# Atmega.net
KiCad netlist of a schematic drawn in EAGLE
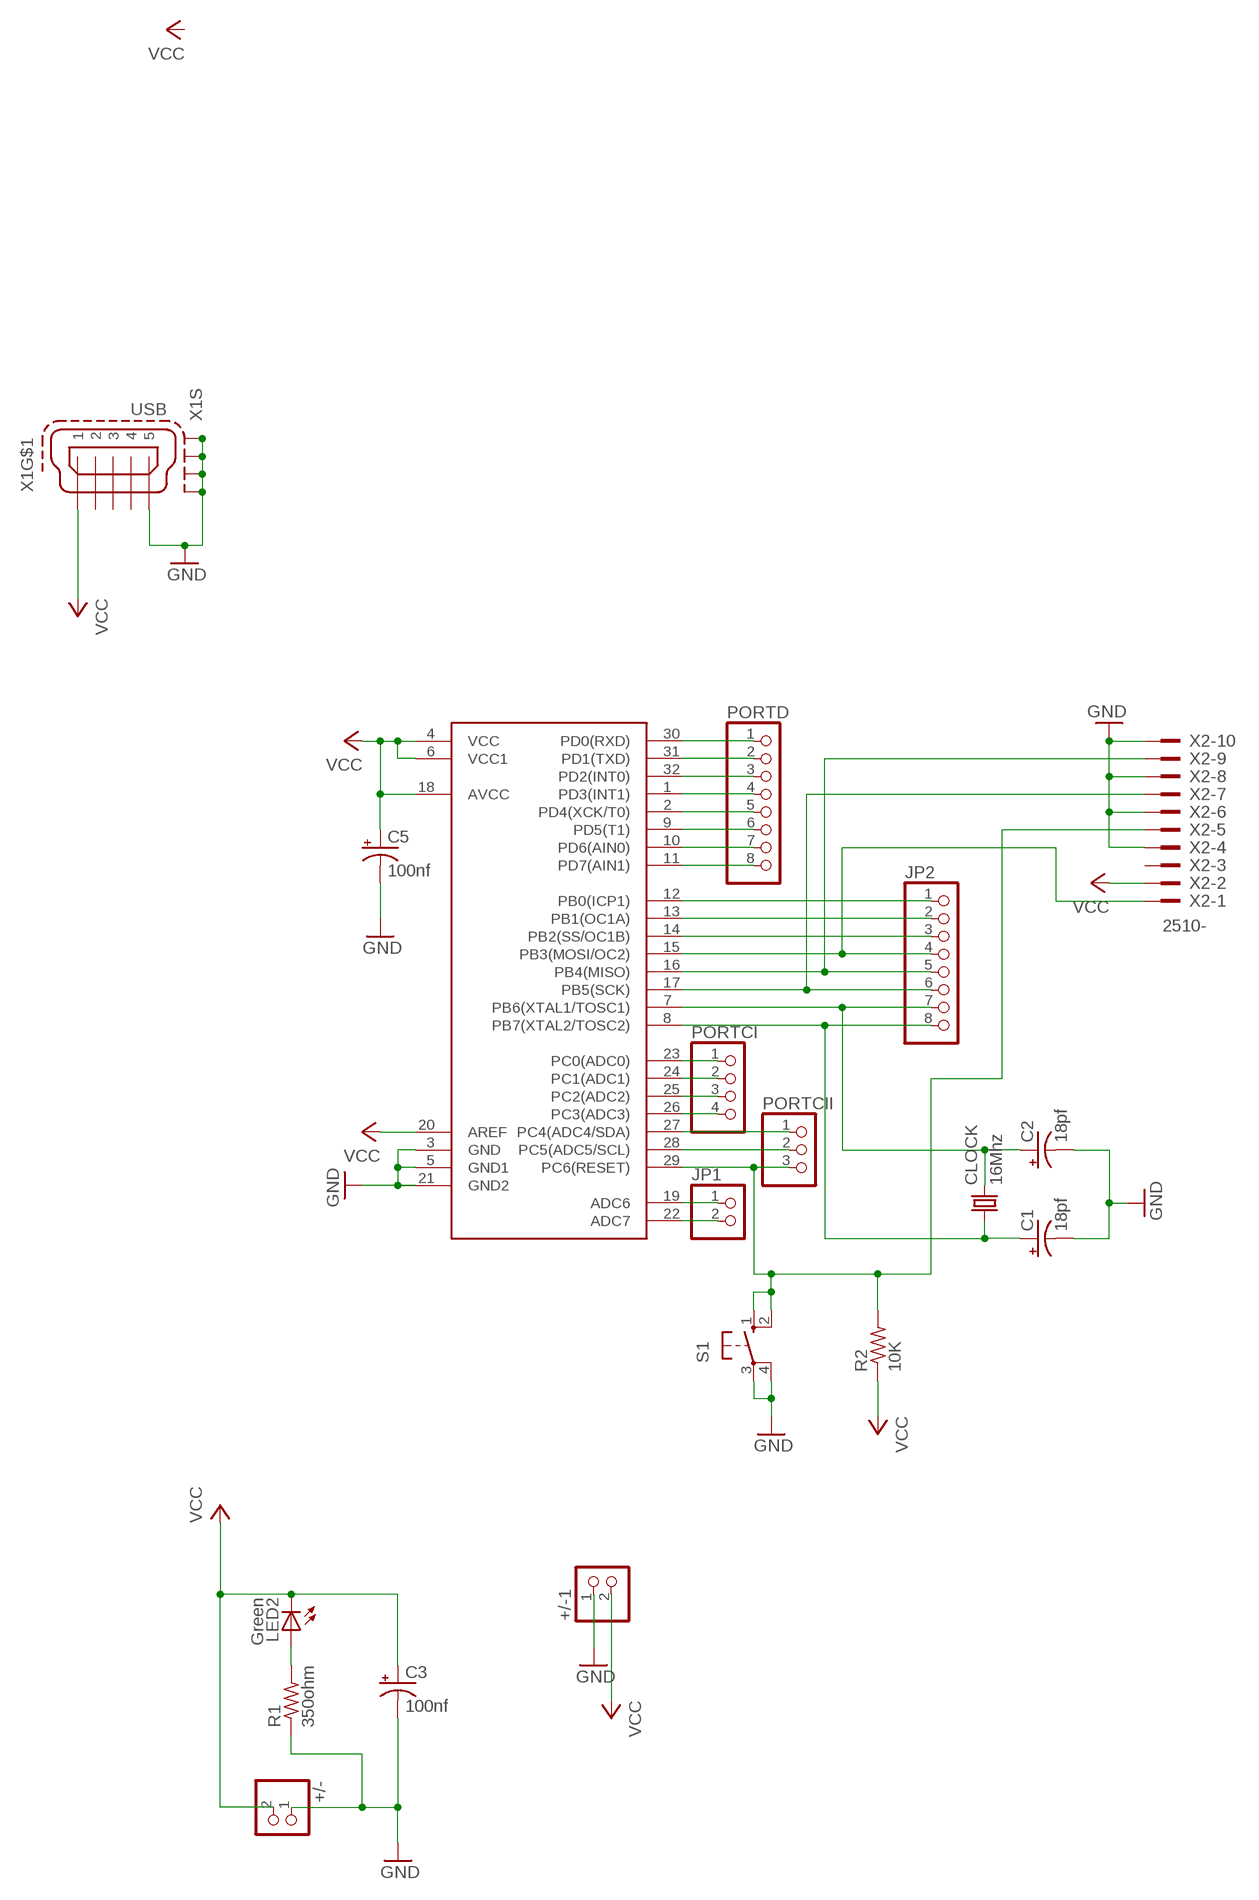
[diagram p0: schematic, sheet 1]

(export (version "E")
  (design (tool "Eeschema 10.0.6"))
  (components
    (comp (ref "+/-")
      (value "PINHD-1X2")
      (footprint "eagle-import:1X02")
      (libsource (lib "eagle-import") (part "PINHD-1X2"))
    )
    (comp (ref "+/-1")
      (value "PINHD-1X2")
      (footprint "eagle-import:1X02")
      (libsource (lib "eagle-import") (part "PINHD-1X2"))
    )
    (comp (ref "C1")
      (value "18pf")
      (footprint "eagle-import:SMC_Z")
      (libsource (lib "eagle-import") (part "CPOL-USSMCZ"))
    )
    (comp (ref "C2")
      (value "18pf")
      (footprint "eagle-import:SMC_Z")
      (libsource (lib "eagle-import") (part "CPOL-USSMCZ"))
    )
    (comp (ref "C3")
      (value "100nf")
      (footprint "eagle-import:SMC_Z")
      (libsource (lib "eagle-import") (part "CPOL-USSMCZ"))
    )
    (comp (ref "C5")
      (value "100nf")
      (footprint "eagle-import:SMC_Z")
      (libsource (lib "eagle-import") (part "CPOL-USSMCZ"))
    )
    (comp (ref "CLOCK")
      (value "16Mhz")
      (footprint "eagle-import:HC49UP")
      (libsource (lib "eagle-import") (part "CRYSTALHC49UP"))
    )
    (comp (ref "JP1")
      (value "PINHD-1X2")
      (footprint "eagle-import:1X02")
      (libsource (lib "eagle-import") (part "PINHD-1X2"))
    )
    (comp (ref "JP2")
      (value "PINHD-1X8")
      (footprint "eagle-import:1X08")
      (libsource (lib "eagle-import") (part "PINHD-1X8"))
    )
    (comp (ref "LED2")
      (value "Green")
      (footprint "eagle-import:PLCC2")
      (fields (field (name "COLOR") "green"))
      (libsource (lib "eagle-import") (part "_T679-?-1E1F1LG"))
    )
    (comp (ref "PORTCI")
      (value "PINHD-1X4")
      (footprint "eagle-import:1X04")
      (libsource (lib "eagle-import") (part "PINHD-1X4"))
    )
    (comp (ref "PORTCII")
      (value "PINHD-1X3")
      (footprint "eagle-import:1X03")
      (libsource (lib "eagle-import") (part "PINHD-1X3"))
    )
    (comp (ref "PORTD")
      (value "PINHD-1X8")
      (footprint "eagle-import:1X08")
      (libsource (lib "eagle-import") (part "PINHD-1X8"))
    )
    (comp (ref "R1")
      (value "350ohm")
      (footprint "eagle-import:M0805")
      (libsource (lib "eagle-import") (part "R-US_M0805"))
    )
    (comp (ref "R2")
      (value "10K")
      (footprint "eagle-import:M0805")
      (libsource (lib "eagle-import") (part "R-US_M0805"))
    )
    (comp (ref "S1")
      (value "10-XX")
      (footprint "eagle-import:B3F-10XX")
      (fields (field (name "MPN") "B3F-1000"))
      (libsource (lib "eagle-import") (part "10-XX"))
    )
    (comp (ref "U$1")
      (value "ATMEGA8A")
      (footprint "eagle-import:TQFP32-08")
      (libsource (lib "eagle-import") (part "ATMEGA8A"))
    )
    (comp (ref "X1")
      (value "USB")
      (footprint "eagle-import:32005-201")
      (libsource (lib "eagle-import") (part "MINI-USB-SCHIELD-32005-201"))
    )
    (comp (ref "X2")
      (value "2510-")
      (footprint "eagle-import:PAK100_2500-10")
      (fields (field (name "MF") "3M") (field (name "MPN") "2510-6002UB"))
      (libsource (lib "eagle-import") (part "2510-"))
    )
  )
  (nets
    (net (code "1") (name "GND") (class "Default")
      (node (ref "+/-") (pin "1") (pinfunction "1_1") (pintype "passive"))
      (node (ref "+/-1") (pin "1") (pinfunction "1_1") (pintype "passive"))
      (node (ref "C1") (pin "-") (pinfunction "-_-") (pintype "passive"))
      (node (ref "C2") (pin "-") (pinfunction "-_-") (pintype "passive"))
      (node (ref "C3") (pin "-") (pinfunction "-_-") (pintype "passive"))
      (node (ref "C5") (pin "-") (pinfunction "-_-") (pintype "passive"))
      (node (ref "R1") (pin "1") (pinfunction "1_1") (pintype "passive"))
      (node (ref "S1") (pin "3") (pinfunction "P_3") (pintype "passive"))
      (node (ref "S1") (pin "4") (pinfunction "P1_4") (pintype "passive"))
      (node (ref "U$1") (pin "21") (pinfunction "GND2_21") (pintype "bidirectional"))
      (node (ref "U$1") (pin "3") (pinfunction "GND_3") (pintype "bidirectional"))
      (node (ref "U$1") (pin "5") (pinfunction "GND1_5") (pintype "bidirectional"))
      (node (ref "X1") (pin "5") (pinfunction "5_5") (pintype "passive"))
      (node (ref "X1") (pin "M1") (pinfunction "S1_M1") (pintype "passive"))
      (node (ref "X1") (pin "M2") (pinfunction "S2_M2") (pintype "passive"))
      (node (ref "X1") (pin "M3") (pinfunction "S3_M3") (pintype "passive"))
      (node (ref "X1") (pin "M4") (pinfunction "S4_M4") (pintype "passive"))
      (node (ref "X2") (pin "10") (pinfunction "KL_10") (pintype "passive"))
      (node (ref "X2") (pin "4") (pinfunction "KL_4") (pintype "passive"))
      (node (ref "X2") (pin "6") (pinfunction "KL_6") (pintype "passive"))
      (node (ref "X2") (pin "8") (pinfunction "KL_8") (pintype "passive"))
    )
    (net (code "2") (name "Net-(LED2-PadA)") (class "Default")
      (node (ref "LED2") (pin "A") (pinfunction "A_A") (pintype "passive"))
      (node (ref "R1") (pin "2") (pinfunction "2_2") (pintype "passive"))
    )
    (net (code "3") (name "Net-(S1-S)") (class "Default")
      (node (ref "PORTCII") (pin "3") (pinfunction "3_3") (pintype "passive"))
      (node (ref "R2") (pin "2") (pinfunction "2_2") (pintype "passive"))
      (node (ref "S1") (pin "1") (pinfunction "S_1") (pintype "passive"))
      (node (ref "S1") (pin "2") (pinfunction "S1_2") (pintype "passive"))
      (node (ref "U$1") (pin "29") (pinfunction "PC6(RESET)_29") (pintype "bidirectional"))
      (node (ref "X2") (pin "5") (pinfunction "KL_5") (pintype "passive"))
    )
    (net (code "4") (name "Net-(U$1-ADC6)") (class "Default")
      (node (ref "JP1") (pin "1") (pinfunction "1_1") (pintype "passive"))
      (node (ref "U$1") (pin "19") (pinfunction "ADC6_19") (pintype "bidirectional"))
    )
    (net (code "5") (name "Net-(U$1-ADC7)") (class "Default")
      (node (ref "JP1") (pin "2") (pinfunction "2_2") (pintype "passive"))
      (node (ref "U$1") (pin "22") (pinfunction "ADC7_22") (pintype "bidirectional"))
    )
    (net (code "6") (name "Net-(U$1-PB0(ICP1))") (class "Default")
      (node (ref "JP2") (pin "1") (pinfunction "1_1") (pintype "passive"))
      (node (ref "U$1") (pin "12") (pinfunction "PB0(ICP1)_12") (pintype "bidirectional"))
    )
    (net (code "7") (name "Net-(U$1-PB1(OC1A))") (class "Default")
      (node (ref "JP2") (pin "2") (pinfunction "2_2") (pintype "passive"))
      (node (ref "U$1") (pin "13") (pinfunction "PB1(OC1A)_13") (pintype "bidirectional"))
    )
    (net (code "8") (name "Net-(U$1-PB2(SS{slash}OC1B))") (class "Default")
      (node (ref "JP2") (pin "3") (pinfunction "3_3") (pintype "passive"))
      (node (ref "U$1") (pin "14") (pinfunction "PB2(SS/OC1B)_14") (pintype "bidirectional"))
    )
    (net (code "9") (name "Net-(U$1-PB3(MOSI{slash}OC2))") (class "Default")
      (node (ref "JP2") (pin "4") (pinfunction "4_4") (pintype "passive"))
      (node (ref "U$1") (pin "15") (pinfunction "PB3(MOSI/OC2)_15") (pintype "bidirectional"))
      (node (ref "X2") (pin "1") (pinfunction "KL_1") (pintype "passive"))
    )
    (net (code "10") (name "Net-(U$1-PB4(MISO))") (class "Default")
      (node (ref "JP2") (pin "5") (pinfunction "5_5") (pintype "passive"))
      (node (ref "U$1") (pin "16") (pinfunction "PB4(MISO)_16") (pintype "bidirectional"))
      (node (ref "X2") (pin "9") (pinfunction "KL_9") (pintype "passive"))
    )
    (net (code "11") (name "Net-(U$1-PB5(SCK))") (class "Default")
      (node (ref "JP2") (pin "6") (pinfunction "6_6") (pintype "passive"))
      (node (ref "U$1") (pin "17") (pinfunction "PB5(SCK)_17") (pintype "bidirectional"))
      (node (ref "X2") (pin "7") (pinfunction "KL_7") (pintype "passive"))
    )
    (net (code "12") (name "Net-(U$1-PB6(XTAL1{slash}TOSC1))") (class "Default")
      (node (ref "C2") (pin "+") (pinfunction "+_+") (pintype "passive"))
      (node (ref "CLOCK") (pin "2") (pinfunction "2_2") (pintype "passive"))
      (node (ref "JP2") (pin "7") (pinfunction "7_7") (pintype "passive"))
      (node (ref "U$1") (pin "7") (pinfunction "PB6(XTAL1/TOSC1)_7") (pintype "bidirectional"))
    )
    (net (code "13") (name "Net-(U$1-PB7(XTAL2{slash}TOSC2))") (class "Default")
      (node (ref "C1") (pin "+") (pinfunction "+_+") (pintype "passive"))
      (node (ref "CLOCK") (pin "1") (pinfunction "1_1") (pintype "passive"))
      (node (ref "JP2") (pin "8") (pinfunction "8_8") (pintype "passive"))
      (node (ref "U$1") (pin "8") (pinfunction "PB7(XTAL2/TOSC2)_8") (pintype "bidirectional"))
    )
    (net (code "14") (name "Net-(U$1-PC0(ADC0))") (class "Default")
      (node (ref "PORTCI") (pin "1") (pinfunction "1_1") (pintype "passive"))
      (node (ref "U$1") (pin "23") (pinfunction "PC0(ADC0)_23") (pintype "bidirectional"))
    )
    (net (code "15") (name "Net-(U$1-PC1(ADC1))") (class "Default")
      (node (ref "PORTCI") (pin "2") (pinfunction "2_2") (pintype "passive"))
      (node (ref "U$1") (pin "24") (pinfunction "PC1(ADC1)_24") (pintype "bidirectional"))
    )
    (net (code "16") (name "Net-(U$1-PC2(ADC2))") (class "Default")
      (node (ref "PORTCI") (pin "3") (pinfunction "3_3") (pintype "passive"))
      (node (ref "U$1") (pin "25") (pinfunction "PC2(ADC2)_25") (pintype "bidirectional"))
    )
    (net (code "17") (name "Net-(U$1-PC3(ADC3))") (class "Default")
      (node (ref "PORTCI") (pin "4") (pinfunction "4_4") (pintype "passive"))
      (node (ref "U$1") (pin "26") (pinfunction "PC3(ADC3)_26") (pintype "bidirectional"))
    )
    (net (code "18") (name "Net-(U$1-PC4(ADC4{slash}SDA))") (class "Default")
      (node (ref "PORTCII") (pin "1") (pinfunction "1_1") (pintype "passive"))
      (node (ref "U$1") (pin "27") (pinfunction "PC4(ADC4/SDA)_27") (pintype "bidirectional"))
    )
    (net (code "19") (name "Net-(U$1-PC5(ADC5{slash}SCL))") (class "Default")
      (node (ref "PORTCII") (pin "2") (pinfunction "2_2") (pintype "passive"))
      (node (ref "U$1") (pin "28") (pinfunction "PC5(ADC5/SCL)_28") (pintype "bidirectional"))
    )
    (net (code "20") (name "Net-(U$1-PD0(RXD))") (class "Default")
      (node (ref "PORTD") (pin "1") (pinfunction "1_1") (pintype "passive"))
      (node (ref "U$1") (pin "30") (pinfunction "PD0(RXD)_30") (pintype "bidirectional"))
    )
    (net (code "21") (name "Net-(U$1-PD1(TXD))") (class "Default")
      (node (ref "PORTD") (pin "2") (pinfunction "2_2") (pintype "passive"))
      (node (ref "U$1") (pin "31") (pinfunction "PD1(TXD)_31") (pintype "bidirectional"))
    )
    (net (code "22") (name "Net-(U$1-PD2(INT0))") (class "Default")
      (node (ref "PORTD") (pin "3") (pinfunction "3_3") (pintype "passive"))
      (node (ref "U$1") (pin "32") (pinfunction "PD2(INT0)_32") (pintype "bidirectional"))
    )
    (net (code "23") (name "Net-(U$1-PD3(INT1))") (class "Default")
      (node (ref "PORTD") (pin "4") (pinfunction "4_4") (pintype "passive"))
      (node (ref "U$1") (pin "1") (pinfunction "PD3(INT1)_1") (pintype "bidirectional"))
    )
    (net (code "24") (name "Net-(U$1-PD4(XCK{slash}T0))") (class "Default")
      (node (ref "PORTD") (pin "5") (pinfunction "5_5") (pintype "passive"))
      (node (ref "U$1") (pin "2") (pinfunction "PD4(XCK/T0)_2") (pintype "bidirectional"))
    )
    (net (code "25") (name "Net-(U$1-PD5(T1))") (class "Default")
      (node (ref "PORTD") (pin "6") (pinfunction "6_6") (pintype "passive"))
      (node (ref "U$1") (pin "9") (pinfunction "PD5(T1)_9") (pintype "bidirectional"))
    )
    (net (code "26") (name "Net-(U$1-PD6(AIN0))") (class "Default")
      (node (ref "PORTD") (pin "7") (pinfunction "7_7") (pintype "passive"))
      (node (ref "U$1") (pin "10") (pinfunction "PD6(AIN0)_10") (pintype "bidirectional"))
    )
    (net (code "27") (name "Net-(U$1-PD7(AIN1))") (class "Default")
      (node (ref "PORTD") (pin "8") (pinfunction "8_8") (pintype "passive"))
      (node (ref "U$1") (pin "11") (pinfunction "PD7(AIN1)_11") (pintype "bidirectional"))
    )
    (net (code "28") (name "VCC") (class "Default")
      (node (ref "+/-") (pin "2") (pinfunction "2_2") (pintype "passive"))
      (node (ref "+/-1") (pin "2") (pinfunction "2_2") (pintype "passive"))
      (node (ref "C3") (pin "+") (pinfunction "+_+") (pintype "passive"))
      (node (ref "C5") (pin "+") (pinfunction "+_+") (pintype "passive"))
      (node (ref "LED2") (pin "C") (pinfunction "C_C") (pintype "passive"))
      (node (ref "R2") (pin "1") (pinfunction "1_1") (pintype "passive"))
      (node (ref "U$1") (pin "18") (pinfunction "AVCC_18") (pintype "bidirectional"))
      (node (ref "U$1") (pin "20") (pinfunction "AREF_20") (pintype "bidirectional"))
      (node (ref "U$1") (pin "4") (pinfunction "VCC_4") (pintype "bidirectional"))
      (node (ref "U$1") (pin "6") (pinfunction "VCC1_6") (pintype "bidirectional"))
      (node (ref "X1") (pin "1") (pinfunction "1_1") (pintype "passive"))
      (node (ref "X2") (pin "2") (pinfunction "KL_2") (pintype "passive"))
    )
    (net (code "29") (name "unconnected-(X1-Pad2)") (class "Default")
      (node (ref "X1") (pin "2") (pinfunction "2_2") (pintype "passive"))
    )
    (net (code "30") (name "unconnected-(X1-Pad3)") (class "Default")
      (node (ref "X1") (pin "3") (pinfunction "3_3") (pintype "passive"))
    )
    (net (code "31") (name "unconnected-(X1-Pad4)") (class "Default")
      (node (ref "X1") (pin "4") (pinfunction "4_4") (pintype "passive"))
    )
    (net (code "32") (name "unconnected-(X2D-KL-Pad3)") (class "Default")
      (node (ref "X2") (pin "3") (pinfunction "KL_3") (pintype "passive"))
    )
  )
)
